# Spectrum-Analyzer.net
KiCad netlist of a schematic drawn in Altium Designer
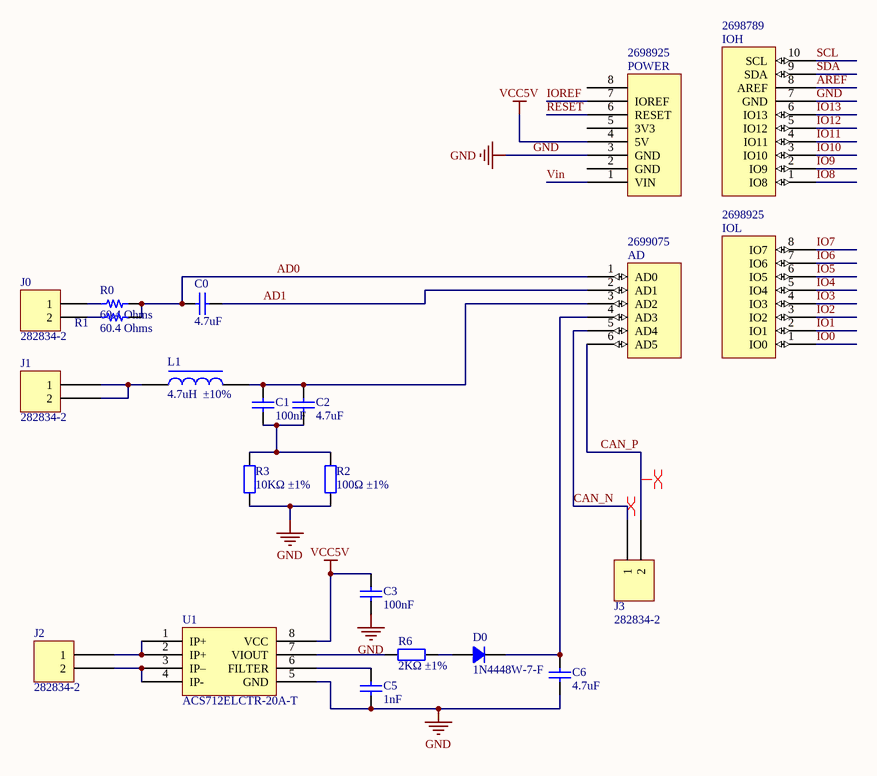
[diagram p0: Spectrum-Analyzer.SchDoc]

(export (version "E")
  (design (tool "Eeschema 10.0.6"))
  (components
    (comp (ref "AD")
      (value "AD")
      (footprint "Header:Header 6x1 8.5mm")
      (fields (field (name "SUPPLIER PART NUMBER 4") "2699075"))
      (libsource (lib "Header") (part "AD"))
    )
    (comp (ref "C0")
      (value "4.7uF")
      (footprint "0805_C")
      (description "Chip capacitors")
      (fields
        (field (name "MANUFACTURER") "Samsung Electro-Mechanics")
        (field (name "PARTNUMBER") "CL21A475KAQNNNE")
      )
      (libsource (lib "Cap") (part "0805 4.7uF (475) 10% 25V"))
    )
    (comp (ref "C1")
      (value "100nF")
      (footprint "0805_C")
      (description "Chip capacitors")
      (fields (field (name "MANUFACTURER") "YAGEO") (field (name "PARTNUMBER") "CC0805KRX7R9BB104"))
      (libsource (lib "Cap") (part "0805 100nF(104) 10% 50V"))
    )
    (comp (ref "C2")
      (value "4.7uF")
      (footprint "0805_C")
      (description "Chip capacitors")
      (fields
        (field (name "MANUFACTURER") "Samsung Electro-Mechanics")
        (field (name "PARTNUMBER") "CL21A475KAQNNNE")
      )
      (libsource (lib "Cap") (part "0805 4.7uF (475) 10% 25V"))
    )
    (comp (ref "C3")
      (value "100nF")
      (footprint "0805_C")
      (description "Chip capacitors")
      (fields (field (name "MANUFACTURER") "YAGEO") (field (name "PARTNUMBER") "CC0805KRX7R9BB104"))
      (libsource (lib "Cap") (part "0805 100nF(104) 10% 50V"))
    )
    (comp (ref "C5")
      (value "1nF")
      (footprint "0805_C")
      (description "Chip capacitors")
      (fields
        (field (name "MANUFACTURER") "Samsung Electro-Mechanics")
        (field (name "PARTNUMBER") "CL21B102KBCNNNC")
      )
      (libsource (lib "Cap") (part "0805 1nF (102) 10% 50V"))
    )
    (comp (ref "C6")
      (value "4.7uF")
      (footprint "0805_C")
      (description "Chip capacitors")
      (fields
        (field (name "MANUFACTURER") "Samsung Electro-Mechanics")
        (field (name "PARTNUMBER") "CL21A475KAQNNNE")
      )
      (libsource (lib "Cap") (part "0805 4.7uF (475) 10% 25V"))
    )
    (comp (ref "D0")
      (value "1N4448W-7-F")
      (footprint "SOD-123")
      (description "DIODE GEN PURP 75V 250MA SOD123")
      (fields (field (name "MANUFACTURER") "Diodes Incorporated"))
      (libsource (lib "Celestial Altium Library - altium_library") (part "Diode"))
    )
    (comp (ref "IOH")
      (value "IOH")
      (footprint "Header:Header 10x1 8.5mm")
      (fields (field (name "SUPPLIER PART NUMBER 3") "2698789"))
      (libsource (lib "Header") (part "IOH"))
    )
    (comp (ref "IOL")
      (value "IOL")
      (footprint "Header 8x1 8.5mm")
      (fields (field (name "SUPPLIER PART NUMBER 4") "2698925"))
      (libsource (lib "Header") (part "IOL"))
    )
    (comp (ref "J0")
      (value "282834-2")
      (footprint "TE 282834-2")
      (description "TERM BLK 2P SIDE ENT 2.54MM PCB")
      (fields (field (name "MANUFACTURER") "TE Connectivity AMP Connectors") (field (name "VOLTAGE") "150V"))
      (libsource (lib "") (part "2 Pin_1"))
    )
    (comp (ref "J1")
      (value "282834-2")
      (footprint "TE 282834-2")
      (description "TERM BLK 2P SIDE ENT 2.54MM PCB")
      (fields (field (name "MANUFACTURER") "TE Connectivity AMP Connectors") (field (name "VOLTAGE") "150V"))
      (libsource (lib "") (part "2 Pin_1"))
    )
    (comp (ref "J2")
      (value "282834-2")
      (footprint "TE 282834-2")
      (description "TERM BLK 2P SIDE ENT 2.54MM PCB")
      (fields (field (name "MANUFACTURER") "TE Connectivity AMP Connectors") (field (name "VOLTAGE") "150V"))
      (libsource (lib "") (part "2 Pin_1"))
    )
    (comp (ref "J3")
      (value "282834-2")
      (footprint "TE 282834-2")
      (description "TERM BLK 2P SIDE ENT 2.54MM PCB")
      (fields (field (name "MANUFACTURER") "TE Connectivity AMP Connectors") (field (name "VOLTAGE") "150V"))
      (libsource (lib "Celestial Altium Library - altium_library") (part "2 Pin"))
    )
    (comp (ref "L1")
      (value "4.7uH  ±10%")
      (footprint "1206_L")
      (description "贴片电感")
      (libsource (lib "IUD") (part "1206 4.7uH  10%"))
    )
    (comp (ref "POWER")
      (value "POWER_UNO")
      (footprint "Header 8x1 8.5mm")
      (fields (field (name "SUPPLIER PART NUMBER 4") "2698925"))
      (libsource (lib "Header") (part "POWER_UNO"))
    )
    (comp (ref "R0")
      (value "~")
      (footprint "RES 0805_2012")
      (description "RES SMD 60.4 OHM 0.1% 1/10W 0805")
      (fields
        (field (name "PART NUMBER") "RN73C2A60R4BTDF")
        (field (name "R1") "60.4 Ohms")
        (field (name "MANUFACTURER") "TE Connectivity Passive Product")
      )
      (libsource (lib "Celestial Altium Library - altium_library") (part "Resistor"))
    )
    (comp (ref "R1")
      (value "60.4 Ohms")
      (footprint "RES 0805_2012")
      (description "RES SMD 60.4 OHM 0.1% 1/10W 0805")
      (fields
        (field (name "PART NUMBER") "RN73C2A60R4BTDF")
        (field (name "MANUFACTURER") "TE Connectivity Passive Product")
      )
      (libsource (lib "Celestial Altium Library - altium_library") (part "Resistor"))
    )
    (comp (ref "R2")
      (value "100Ω ±1%")
      (footprint "0805_R")
      (description "Chip resistor")
      (fields (field (name "MANUFACTURER") "Uniroyal Elec") (field (name "POWER") "1/8W"))
      (libsource (lib "RES") (part "0805 100R (1000) 1%"))
    )
    (comp (ref "R3")
      (value "10KΩ ±1%")
      (footprint "0805_R")
      (description "Chip resistor")
      (fields (field (name "MANUFACTURER") "Uniroyal Elec") (field (name "PARTNUMBER") "0805W8F1002T5E"))
      (libsource (lib "RES") (part "0805 10K (1002) 1%"))
    )
    (comp (ref "R6")
      (value "2KΩ ±1%")
      (footprint "0805_R")
      (description "Chip resistor")
      (fields (field (name "MANUFACTURER") "Uniroyal Elec") (field (name "POWER") "1/8W"))
      (libsource (lib "RES") (part "0805 2K (2001) 1%"))
    )
    (comp (ref "U1")
      (value "ACS712ELCTR-20A-T")
      (footprint "SOIC-8_150mil")
      (description "传感器")
      (libsource (lib "Miscellaneous Devices LC") (part "ACS712ELCTR-20A-T_[C10681]"))
    )
  )
  (nets
    (net (code "2") (name "/AD0") (class "Default")
      (node (ref "AD") (pin "1") (pinfunction "AD0_1") (pintype "bidirectional"))
      (node (ref "C0") (pin "2") (pinfunction "2_2") (pintype "passive"))
      (node (ref "R0") (pin "2") (pinfunction "2_2") (pintype "passive"))
      (node (ref "R1") (pin "2") (pinfunction "2_2") (pintype "passive"))
    )
    (net (code "3") (name "/AD1") (class "Default")
      (node (ref "AD") (pin "2") (pinfunction "AD1_2") (pintype "bidirectional"))
      (node (ref "C0") (pin "1") (pinfunction "1_1") (pintype "passive"))
    )
    (net (code "4") (name "/AREF") (class "Default")
      (node (ref "IOH") (pin "8") (pinfunction "AREF_8") (pintype "passive"))
    )
    (net (code "5") (name "/CAN_N") (class "Default")
      (node (ref "AD") (pin "5") (pinfunction "AD4_5") (pintype "bidirectional"))
      (node (ref "J3") (pin "1") (pinfunction "1_1") (pintype "passive"))
    )
    (net (code "6") (name "/CAN_P") (class "Default")
      (node (ref "AD") (pin "6") (pinfunction "AD5_6") (pintype "bidirectional"))
      (node (ref "J3") (pin "2") (pinfunction "2_2") (pintype "passive"))
    )
    (net (code "7") (name "/IO0") (class "Default")
      (node (ref "IOL") (pin "1") (pinfunction "IO0_1") (pintype "bidirectional"))
    )
    (net (code "8") (name "/IO1") (class "Default")
      (node (ref "IOL") (pin "2") (pinfunction "IO1_2") (pintype "bidirectional"))
    )
    (net (code "9") (name "/IO2") (class "Default")
      (node (ref "IOL") (pin "3") (pinfunction "IO2_3") (pintype "bidirectional"))
    )
    (net (code "10") (name "/IO3") (class "Default")
      (node (ref "IOL") (pin "4") (pinfunction "IO3_4") (pintype "bidirectional"))
    )
    (net (code "11") (name "/IO4") (class "Default")
      (node (ref "IOL") (pin "5") (pinfunction "IO4_5") (pintype "bidirectional"))
    )
    (net (code "12") (name "/IO5") (class "Default")
      (node (ref "IOL") (pin "6") (pinfunction "IO5_6") (pintype "bidirectional"))
    )
    (net (code "13") (name "/IO6") (class "Default")
      (node (ref "IOL") (pin "7") (pinfunction "IO6_7") (pintype "bidirectional"))
    )
    (net (code "14") (name "/IO7") (class "Default")
      (node (ref "IOL") (pin "8") (pinfunction "IO7_8") (pintype "bidirectional"))
    )
    (net (code "15") (name "/IO8") (class "Default")
      (node (ref "IOH") (pin "1") (pinfunction "IO8_1") (pintype "bidirectional"))
    )
    (net (code "16") (name "/IO9") (class "Default")
      (node (ref "IOH") (pin "2") (pinfunction "IO9_2") (pintype "bidirectional"))
    )
    (net (code "17") (name "/IO10") (class "Default")
      (node (ref "IOH") (pin "3") (pinfunction "IO10_3") (pintype "bidirectional"))
    )
    (net (code "18") (name "/IO11") (class "Default")
      (node (ref "IOH") (pin "4") (pinfunction "IO11_4") (pintype "bidirectional"))
    )
    (net (code "19") (name "/IO12") (class "Default")
      (node (ref "IOH") (pin "5") (pinfunction "IO12_5") (pintype "bidirectional"))
    )
    (net (code "20") (name "/IO13") (class "Default")
      (node (ref "IOH") (pin "6") (pinfunction "IO13_6") (pintype "bidirectional"))
    )
    (net (code "21") (name "/IOREF") (class "Default")
      (node (ref "POWER") (pin "7") (pinfunction "IOREF_7") (pintype "power_in"))
    )
    (net (code "22") (name "/RESET") (class "Default")
      (node (ref "POWER") (pin "6") (pinfunction "RESET_6") (pintype "passive"))
    )
    (net (code "23") (name "/SCL") (class "Default")
      (node (ref "IOH") (pin "10") (pinfunction "SCL_10") (pintype "bidirectional"))
    )
    (net (code "24") (name "/SDA") (class "Default")
      (node (ref "IOH") (pin "9") (pinfunction "SDA_9") (pintype "bidirectional"))
    )
    (net (code "25") (name "/Vin") (class "Default")
      (node (ref "POWER") (pin "1") (pinfunction "VIN_1") (pintype "power_in"))
    )
    (net (code "26") (name "GND") (class "Default")
      (node (ref "C3") (pin "1") (pinfunction "1_1") (pintype "passive"))
      (node (ref "C5") (pin "1") (pinfunction "1_1") (pintype "passive"))
      (node (ref "C6") (pin "1") (pinfunction "1_1") (pintype "passive"))
      (node (ref "IOH") (pin "7") (pinfunction "GND_7") (pintype "power_in"))
      (node (ref "POWER") (pin "3") (pinfunction "GND_3") (pintype "power_in"))
      (node (ref "R2") (pin "1") (pinfunction "1_1") (pintype "passive"))
      (node (ref "R3") (pin "1") (pinfunction "1_1") (pintype "passive"))
      (node (ref "U1") (pin "5") (pinfunction "GND_5") (pintype "passive"))
    )
    (net (code "27") (name "Net-(AD-AD2)") (class "Default")
      (node (ref "AD") (pin "3") (pinfunction "AD2_3") (pintype "bidirectional"))
      (node (ref "C1") (pin "2") (pinfunction "2_2") (pintype "passive"))
      (node (ref "C2") (pin "2") (pinfunction "2_2") (pintype "passive"))
      (node (ref "L1") (pin "2") (pinfunction "2_2") (pintype "passive"))
    )
    (net (code "28") (name "Net-(AD-AD3)") (class "Default")
      (node (ref "AD") (pin "4") (pinfunction "AD3_4") (pintype "bidirectional"))
      (node (ref "C6") (pin "2") (pinfunction "2_2") (pintype "passive"))
      (node (ref "D0") (pin "2") (pinfunction "2_2") (pintype "passive"))
    )
    (net (code "29") (name "Net-(C1-Pad1)") (class "Default")
      (node (ref "C1") (pin "1") (pinfunction "1_1") (pintype "passive"))
      (node (ref "C2") (pin "1") (pinfunction "1_1") (pintype "passive"))
      (node (ref "R2") (pin "2") (pinfunction "2_2") (pintype "passive"))
      (node (ref "R3") (pin "2") (pinfunction "2_2") (pintype "passive"))
    )
    (net (code "30") (name "Net-(D0-Pad1)") (class "Default")
      (node (ref "D0") (pin "1") (pinfunction "1_1") (pintype "passive"))
      (node (ref "R6") (pin "2") (pinfunction "2_2") (pintype "passive"))
    )
    (net (code "31") (name "Net-(J0-Pad1)") (class "Default")
      (node (ref "J0") (pin "1") (pinfunction "1_1") (pintype "passive"))
      (node (ref "R0") (pin "1") (pinfunction "1_1") (pintype "passive"))
    )
    (net (code "32") (name "Net-(J0-Pad2)") (class "Default")
      (node (ref "J0") (pin "2") (pinfunction "2_2") (pintype "passive"))
      (node (ref "R1") (pin "1") (pinfunction "1_1") (pintype "passive"))
    )
    (net (code "33") (name "Net-(J1-Pad1)") (class "Default")
      (node (ref "J1") (pin "1") (pinfunction "1_1") (pintype "passive"))
      (node (ref "J1") (pin "2") (pinfunction "2_2") (pintype "passive"))
      (node (ref "L1") (pin "1") (pinfunction "1_1") (pintype "passive"))
    )
    (net (code "34") (name "Net-(J2-Pad1)") (class "Default")
      (node (ref "J2") (pin "1") (pinfunction "1_1") (pintype "passive"))
      (node (ref "U1") (pin "1") (pinfunction "IP+_1") (pintype "passive"))
      (node (ref "U1") (pin "2") (pinfunction "IP+_2") (pintype "passive"))
    )
    (net (code "35") (name "Net-(U1-FILTER)") (class "Default")
      (node (ref "C5") (pin "2") (pinfunction "2_2") (pintype "passive"))
      (node (ref "U1") (pin "6") (pinfunction "FILTER_6") (pintype "passive"))
    )
    (net (code "36") (name "Net-(U1-IP-)") (class "Default")
      (node (ref "J2") (pin "2") (pinfunction "2_2") (pintype "passive"))
      (node (ref "U1") (pin "3") (pinfunction "IP–_3") (pintype "passive"))
      (node (ref "U1") (pin "4") (pinfunction "IP-_4") (pintype "passive"))
    )
    (net (code "37") (name "Net-(U1-VIOUT)") (class "Default")
      (node (ref "R6") (pin "1") (pinfunction "1_1") (pintype "passive"))
      (node (ref "U1") (pin "7") (pinfunction "VIOUT_7") (pintype "passive"))
    )
    (net (code "38") (name "VCC5V") (class "Default")
      (node (ref "C3") (pin "2") (pinfunction "2_2") (pintype "passive"))
      (node (ref "POWER") (pin "4") (pinfunction "5V_4") (pintype "power_in"))
      (node (ref "U1") (pin "8") (pinfunction "VCC_8") (pintype "passive"))
    )
    (net (code "39") (name "unconnected-(POWER-3V3-Pad5)") (class "Default")
      (node (ref "POWER") (pin "5") (pinfunction "3V3_5") (pintype "power_in"))
    )
    (net (code "40") (name "unconnected-(POWER-GND-Pad2)") (class "Default")
      (node (ref "POWER") (pin "2") (pinfunction "GND_2") (pintype "power_in"))
    )
    (net (code "41") (name "unconnected-(POWER-Pad8)") (class "Default")
      (node (ref "POWER") (pin "8") (pintype "passive"))
    )
  )
)
